# FPGA.net
KiCad netlist of a schematic drawn in Altium Designer
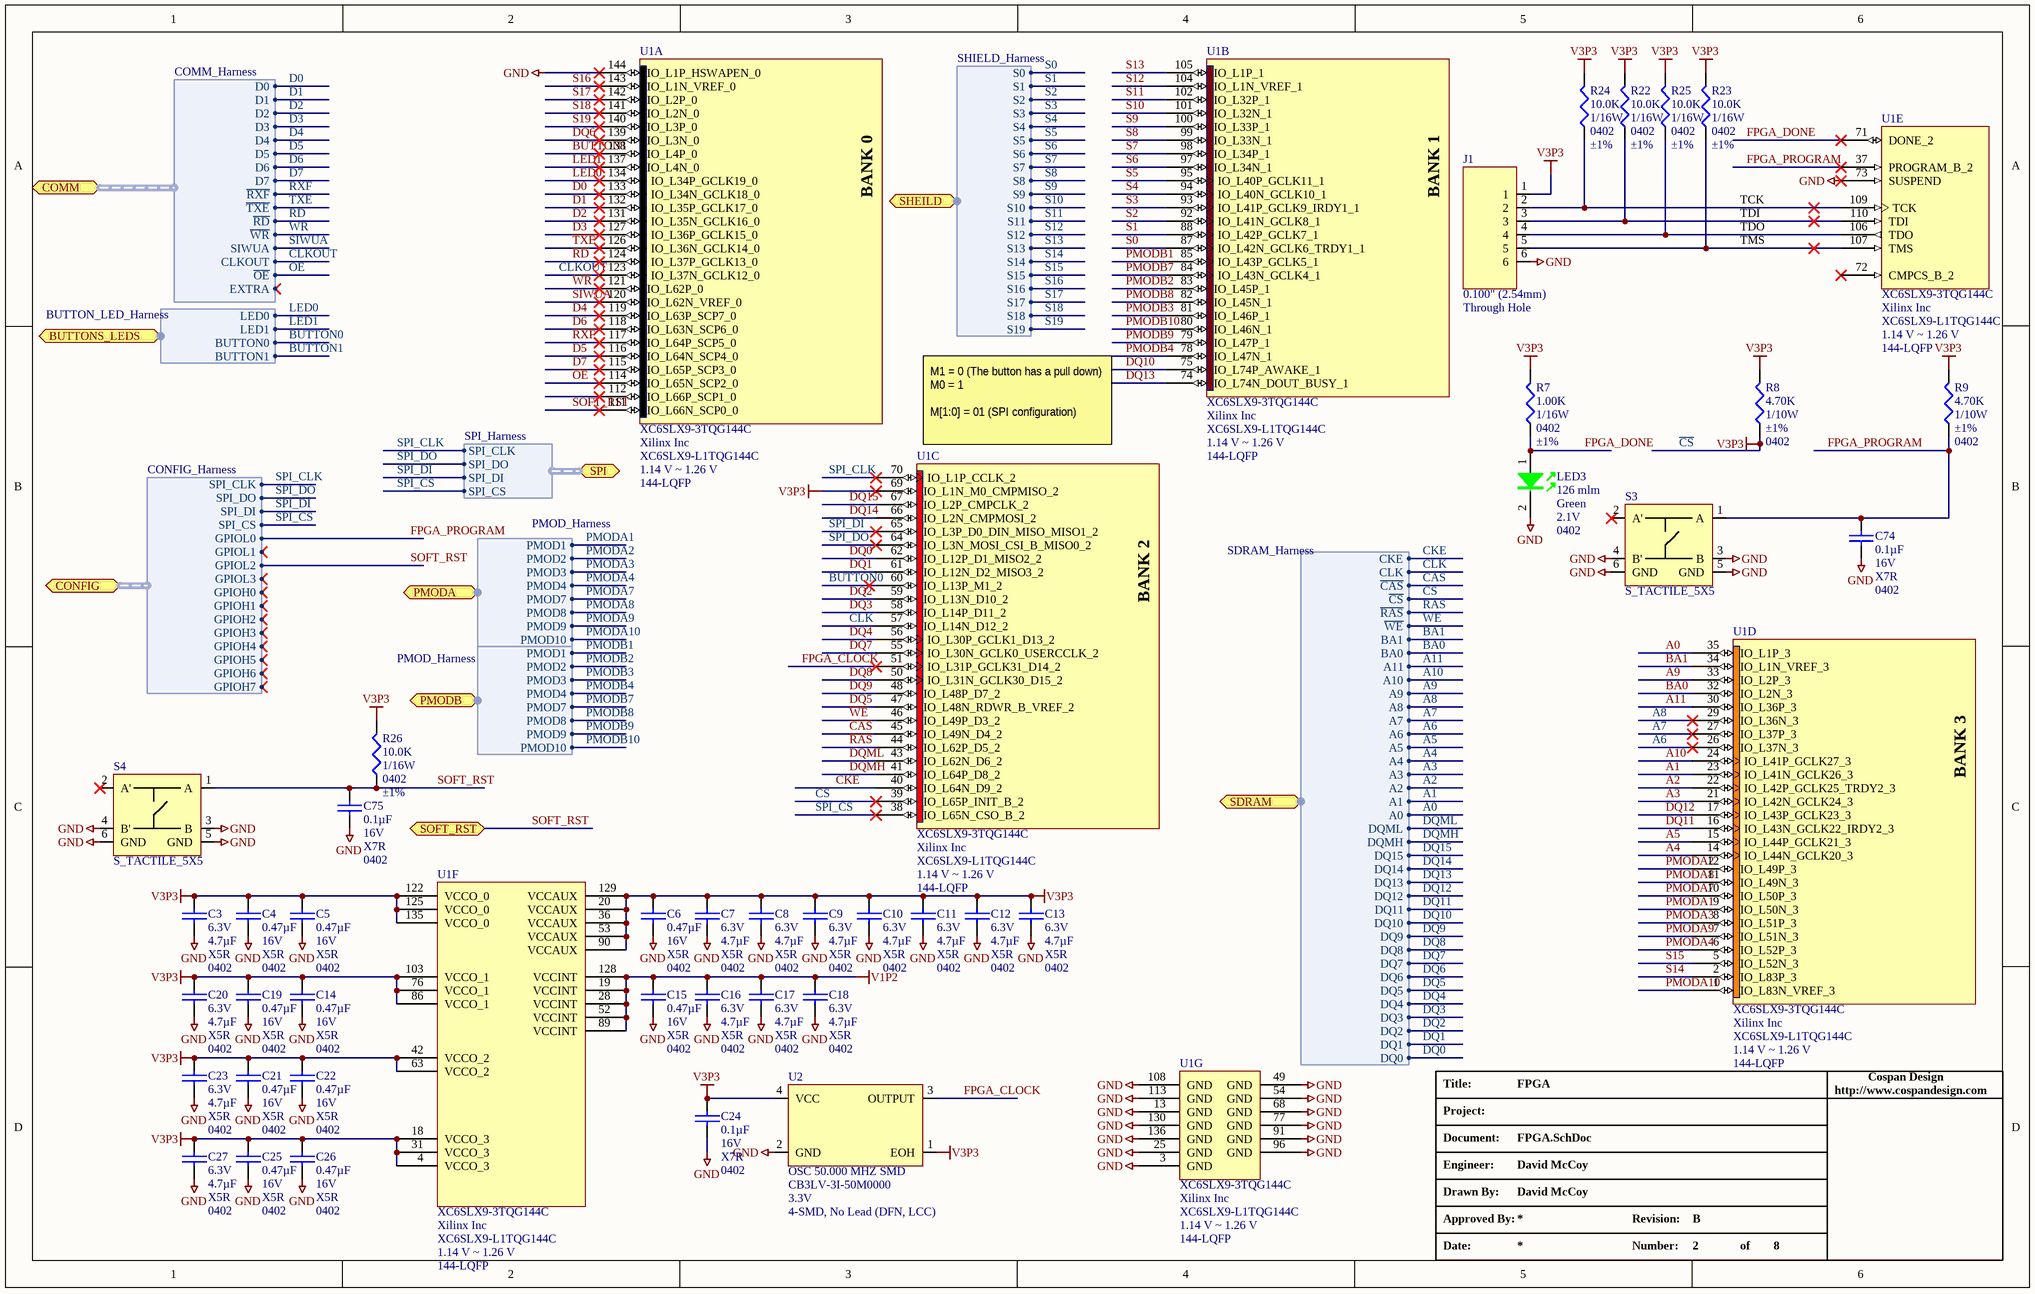
[diagram p0: FPGA.SchDoc]

(export (version "E")
  (design (tool "Eeschema 10.0.6"))
  (components
    (comp (ref "C3")
      (value "4.7uF")
      (footprint "C_ERA-0402")
      (description "CAP CER 4.7UF 6.3V X5R 0402")
      (fields
        (field (name "MANUFACTURER") "Murata Electronics North America")
        (field (name "MANUFACTURER PART NUMBER") "GRM155R60J475ME87D")
        (field (name "VOLTAGE - RATED") "6.3V")
        (field (name "CAPACITANCE") "4.7µF")
        (field (name "TEMPERATURE COEFFICIENT") "X5R")
        (field (name "PACKAGE / CASE") "0402")
      )
      (libsource (lib "Main LibraryX") (part "C_0402_4.7UF"))
    )
    (comp (ref "C4")
      (value "0.47uF")
      (footprint "C_ERA-0402")
      (description "CAP CER .47UF 16V X5R 0402")
      (fields
        (field (name "TOLERANCE") "±10%")
        (field (name "MANUFACTURER") "TDK Corporation")
        (field (name "CAPACITANCE") "0.47µF")
        (field (name "VOLTAGE - RATED") "16V")
        (field (name "TEMPERATURE COEFFICIENT") "X5R")
        (field (name "PACKAGE / CASE") "0402")
      )
      (libsource (lib "Main LibraryX") (part "C_0402_0.47UF"))
    )
    (comp (ref "C5")
      (value "0.47uF")
      (footprint "C_ERA-0402")
      (description "CAP CER .47UF 16V X5R 0402")
      (fields
        (field (name "TOLERANCE") "±10%")
        (field (name "MANUFACTURER") "TDK Corporation")
        (field (name "CAPACITANCE") "0.47µF")
        (field (name "VOLTAGE - RATED") "16V")
        (field (name "TEMPERATURE COEFFICIENT") "X5R")
        (field (name "PACKAGE / CASE") "0402")
      )
      (libsource (lib "Main LibraryX") (part "C_0402_0.47UF"))
    )
    (comp (ref "C6")
      (value "0.47uF")
      (footprint "C_ERA-0402")
      (description "CAP CER .47UF 16V X5R 0402")
      (fields
        (field (name "TOLERANCE") "±10%")
        (field (name "MANUFACTURER") "TDK Corporation")
        (field (name "CAPACITANCE") "0.47µF")
        (field (name "VOLTAGE - RATED") "16V")
        (field (name "TEMPERATURE COEFFICIENT") "X5R")
        (field (name "PACKAGE / CASE") "0402")
      )
      (libsource (lib "Main LibraryX") (part "C_0402_0.47UF"))
    )
    (comp (ref "C7")
      (value "4.7uF")
      (footprint "C_ERA-0402")
      (description "CAP CER 4.7UF 6.3V X5R 0402")
      (fields
        (field (name "MANUFACTURER") "Murata Electronics North America")
        (field (name "MANUFACTURER PART NUMBER") "GRM155R60J475ME87D")
        (field (name "VOLTAGE - RATED") "6.3V")
        (field (name "CAPACITANCE") "4.7µF")
        (field (name "TEMPERATURE COEFFICIENT") "X5R")
        (field (name "PACKAGE / CASE") "0402")
      )
      (libsource (lib "Main LibraryX") (part "C_0402_4.7UF"))
    )
    (comp (ref "C8")
      (value "4.7uF")
      (footprint "C_ERA-0402")
      (description "CAP CER 4.7UF 6.3V X5R 0402")
      (fields
        (field (name "MANUFACTURER") "Murata Electronics North America")
        (field (name "MANUFACTURER PART NUMBER") "GRM155R60J475ME87D")
        (field (name "VOLTAGE - RATED") "6.3V")
        (field (name "CAPACITANCE") "4.7µF")
        (field (name "TEMPERATURE COEFFICIENT") "X5R")
        (field (name "PACKAGE / CASE") "0402")
      )
      (libsource (lib "Main LibraryX") (part "C_0402_4.7UF"))
    )
    (comp (ref "C9")
      (value "4.7uF")
      (footprint "C_ERA-0402")
      (description "CAP CER 4.7UF 6.3V X5R 0402")
      (fields
        (field (name "MANUFACTURER") "Murata Electronics North America")
        (field (name "MANUFACTURER PART NUMBER") "GRM155R60J475ME87D")
        (field (name "VOLTAGE - RATED") "6.3V")
        (field (name "CAPACITANCE") "4.7µF")
        (field (name "TEMPERATURE COEFFICIENT") "X5R")
        (field (name "PACKAGE / CASE") "0402")
      )
      (libsource (lib "Main LibraryX") (part "C_0402_4.7UF"))
    )
    (comp (ref "C10")
      (value "4.7uF")
      (footprint "C_ERA-0402")
      (description "CAP CER 4.7UF 6.3V X5R 0402")
      (fields
        (field (name "MANUFACTURER") "Murata Electronics North America")
        (field (name "MANUFACTURER PART NUMBER") "GRM155R60J475ME87D")
        (field (name "VOLTAGE - RATED") "6.3V")
        (field (name "CAPACITANCE") "4.7µF")
        (field (name "TEMPERATURE COEFFICIENT") "X5R")
        (field (name "PACKAGE / CASE") "0402")
      )
      (libsource (lib "Main LibraryX") (part "C_0402_4.7UF"))
    )
    (comp (ref "C11")
      (value "4.7uF")
      (footprint "C_ERA-0402")
      (description "CAP CER 4.7UF 6.3V X5R 0402")
      (fields
        (field (name "MANUFACTURER") "Murata Electronics North America")
        (field (name "MANUFACTURER PART NUMBER") "GRM155R60J475ME87D")
        (field (name "VOLTAGE - RATED") "6.3V")
        (field (name "CAPACITANCE") "4.7µF")
        (field (name "TEMPERATURE COEFFICIENT") "X5R")
        (field (name "PACKAGE / CASE") "0402")
      )
      (libsource (lib "Main LibraryX") (part "C_0402_4.7UF"))
    )
    (comp (ref "C12")
      (value "4.7uF")
      (footprint "C_ERA-0402")
      (description "CAP CER 4.7UF 6.3V X5R 0402")
      (fields
        (field (name "MANUFACTURER") "Murata Electronics North America")
        (field (name "MANUFACTURER PART NUMBER") "GRM155R60J475ME87D")
        (field (name "VOLTAGE - RATED") "6.3V")
        (field (name "CAPACITANCE") "4.7µF")
        (field (name "TEMPERATURE COEFFICIENT") "X5R")
        (field (name "PACKAGE / CASE") "0402")
      )
      (libsource (lib "Main LibraryX") (part "C_0402_4.7UF"))
    )
    (comp (ref "C13")
      (value "4.7uF")
      (footprint "C_ERA-0402")
      (description "CAP CER 4.7UF 6.3V X5R 0402")
      (fields
        (field (name "MANUFACTURER") "Murata Electronics North America")
        (field (name "MANUFACTURER PART NUMBER") "GRM155R60J475ME87D")
        (field (name "VOLTAGE - RATED") "6.3V")
        (field (name "CAPACITANCE") "4.7µF")
        (field (name "TEMPERATURE COEFFICIENT") "X5R")
        (field (name "PACKAGE / CASE") "0402")
      )
      (libsource (lib "Main LibraryX") (part "C_0402_4.7UF"))
    )
    (comp (ref "C14")
      (value "0.47uF")
      (footprint "C_ERA-0402")
      (description "CAP CER .47UF 16V X5R 0402")
      (fields
        (field (name "TOLERANCE") "±10%")
        (field (name "MANUFACTURER") "TDK Corporation")
        (field (name "CAPACITANCE") "0.47µF")
        (field (name "VOLTAGE - RATED") "16V")
        (field (name "TEMPERATURE COEFFICIENT") "X5R")
        (field (name "PACKAGE / CASE") "0402")
      )
      (libsource (lib "Main LibraryX") (part "C_0402_0.47UF"))
    )
    (comp (ref "C15")
      (value "0.47uF")
      (footprint "C_ERA-0402")
      (description "CAP CER .47UF 16V X5R 0402")
      (fields
        (field (name "TOLERANCE") "±10%")
        (field (name "MANUFACTURER") "TDK Corporation")
        (field (name "CAPACITANCE") "0.47µF")
        (field (name "VOLTAGE - RATED") "16V")
        (field (name "TEMPERATURE COEFFICIENT") "X5R")
        (field (name "PACKAGE / CASE") "0402")
      )
      (libsource (lib "Main LibraryX") (part "C_0402_0.47UF"))
    )
    (comp (ref "C16")
      (value "4.7uF")
      (footprint "C_ERA-0402")
      (description "CAP CER 4.7UF 6.3V X5R 0402")
      (fields
        (field (name "MANUFACTURER") "Murata Electronics North America")
        (field (name "MANUFACTURER PART NUMBER") "GRM155R60J475ME87D")
        (field (name "VOLTAGE - RATED") "6.3V")
        (field (name "CAPACITANCE") "4.7µF")
        (field (name "TEMPERATURE COEFFICIENT") "X5R")
        (field (name "PACKAGE / CASE") "0402")
      )
      (libsource (lib "Main LibraryX") (part "C_0402_4.7UF"))
    )
    (comp (ref "C17")
      (value "4.7uF")
      (footprint "C_ERA-0402")
      (description "CAP CER 4.7UF 6.3V X5R 0402")
      (fields
        (field (name "MANUFACTURER") "Murata Electronics North America")
        (field (name "MANUFACTURER PART NUMBER") "GRM155R60J475ME87D")
        (field (name "VOLTAGE - RATED") "6.3V")
        (field (name "CAPACITANCE") "4.7µF")
        (field (name "TEMPERATURE COEFFICIENT") "X5R")
        (field (name "PACKAGE / CASE") "0402")
      )
      (libsource (lib "Main LibraryX") (part "C_0402_4.7UF"))
    )
    (comp (ref "C18")
      (value "4.7uF")
      (footprint "C_ERA-0402")
      (description "CAP CER 4.7UF 6.3V X5R 0402")
      (fields
        (field (name "MANUFACTURER") "Murata Electronics North America")
        (field (name "MANUFACTURER PART NUMBER") "GRM155R60J475ME87D")
        (field (name "VOLTAGE - RATED") "6.3V")
        (field (name "CAPACITANCE") "4.7µF")
        (field (name "TEMPERATURE COEFFICIENT") "X5R")
        (field (name "PACKAGE / CASE") "0402")
      )
      (libsource (lib "Main LibraryX") (part "C_0402_4.7UF"))
    )
    (comp (ref "C19")
      (value "0.47uF")
      (footprint "C_ERA-0402")
      (description "CAP CER .47UF 16V X5R 0402")
      (fields
        (field (name "TOLERANCE") "±10%")
        (field (name "MANUFACTURER") "TDK Corporation")
        (field (name "CAPACITANCE") "0.47µF")
        (field (name "VOLTAGE - RATED") "16V")
        (field (name "TEMPERATURE COEFFICIENT") "X5R")
        (field (name "PACKAGE / CASE") "0402")
      )
      (libsource (lib "Main LibraryX") (part "C_0402_0.47UF"))
    )
    (comp (ref "C20")
      (value "4.7uF")
      (footprint "C_ERA-0402")
      (description "CAP CER 4.7UF 6.3V X5R 0402")
      (fields
        (field (name "MANUFACTURER") "Murata Electronics North America")
        (field (name "MANUFACTURER PART NUMBER") "GRM155R60J475ME87D")
        (field (name "VOLTAGE - RATED") "6.3V")
        (field (name "CAPACITANCE") "4.7µF")
        (field (name "TEMPERATURE COEFFICIENT") "X5R")
        (field (name "PACKAGE / CASE") "0402")
      )
      (libsource (lib "Main LibraryX") (part "C_0402_4.7UF"))
    )
    (comp (ref "C21")
      (value "0.47uF")
      (footprint "C_ERA-0402")
      (description "CAP CER .47UF 16V X5R 0402")
      (fields
        (field (name "TOLERANCE") "±10%")
        (field (name "MANUFACTURER") "TDK Corporation")
        (field (name "CAPACITANCE") "0.47µF")
        (field (name "VOLTAGE - RATED") "16V")
        (field (name "TEMPERATURE COEFFICIENT") "X5R")
        (field (name "PACKAGE / CASE") "0402")
      )
      (libsource (lib "Main LibraryX") (part "C_0402_0.47UF"))
    )
    (comp (ref "C22")
      (value "0.47uF")
      (footprint "C_ERA-0402")
      (description "CAP CER .47UF 16V X5R 0402")
      (fields
        (field (name "TOLERANCE") "±10%")
        (field (name "MANUFACTURER") "TDK Corporation")
        (field (name "CAPACITANCE") "0.47µF")
        (field (name "VOLTAGE - RATED") "16V")
        (field (name "TEMPERATURE COEFFICIENT") "X5R")
        (field (name "PACKAGE / CASE") "0402")
      )
      (libsource (lib "Main LibraryX") (part "C_0402_0.47UF"))
    )
    (comp (ref "C23")
      (value "4.7uF")
      (footprint "C_ERA-0402")
      (description "CAP CER 4.7UF 6.3V X5R 0402")
      (fields
        (field (name "MANUFACTURER") "Murata Electronics North America")
        (field (name "MANUFACTURER PART NUMBER") "GRM155R60J475ME87D")
        (field (name "VOLTAGE - RATED") "6.3V")
        (field (name "CAPACITANCE") "4.7µF")
        (field (name "TEMPERATURE COEFFICIENT") "X5R")
        (field (name "PACKAGE / CASE") "0402")
      )
      (libsource (lib "Main LibraryX") (part "C_0402_4.7UF"))
    )
    (comp (ref "C24")
      (value "0.1uF")
      (footprint "C_ERA-0402")
      (description "CAP CER .10UF 16V X7R 0402")
      (fields
        (field (name "MANUFACTURER") "TDK Corporation")
        (field (name "MANUFACTURER PART NUMBER") "C1005X7R1C104K")
        (field (name "CAPACITANCE") "0.1µF")
        (field (name "VOLTAGE - RATED") "16V")
        (field (name "TEMPERATURE COEFFICIENT") "X7R")
        (field (name "PACKAGE / CASE") "0402")
      )
      (libsource (lib "Main LibraryX") (part "C_0402_0.1UF_16V"))
    )
    (comp (ref "C25")
      (value "0.47uF")
      (footprint "C_ERA-0402")
      (description "CAP CER .47UF 16V X5R 0402")
      (fields
        (field (name "TOLERANCE") "±10%")
        (field (name "MANUFACTURER") "TDK Corporation")
        (field (name "CAPACITANCE") "0.47µF")
        (field (name "VOLTAGE - RATED") "16V")
        (field (name "TEMPERATURE COEFFICIENT") "X5R")
        (field (name "PACKAGE / CASE") "0402")
      )
      (libsource (lib "Main LibraryX") (part "C_0402_0.47UF"))
    )
    (comp (ref "C26")
      (value "0.47uF")
      (footprint "C_ERA-0402")
      (description "CAP CER .47UF 16V X5R 0402")
      (fields
        (field (name "TOLERANCE") "±10%")
        (field (name "MANUFACTURER") "TDK Corporation")
        (field (name "CAPACITANCE") "0.47µF")
        (field (name "VOLTAGE - RATED") "16V")
        (field (name "TEMPERATURE COEFFICIENT") "X5R")
        (field (name "PACKAGE / CASE") "0402")
      )
      (libsource (lib "Main LibraryX") (part "C_0402_0.47UF"))
    )
    (comp (ref "C27")
      (value "4.7uF")
      (footprint "C_ERA-0402")
      (description "CAP CER 4.7UF 6.3V X5R 0402")
      (fields
        (field (name "MANUFACTURER") "Murata Electronics North America")
        (field (name "MANUFACTURER PART NUMBER") "GRM155R60J475ME87D")
        (field (name "VOLTAGE - RATED") "6.3V")
        (field (name "CAPACITANCE") "4.7µF")
        (field (name "TEMPERATURE COEFFICIENT") "X5R")
        (field (name "PACKAGE / CASE") "0402")
      )
      (libsource (lib "Main LibraryX") (part "C_0402_4.7UF"))
    )
    (comp (ref "C74")
      (value "0.1uF")
      (footprint "C_ERA-0402")
      (description "CAP CER .10UF 16V X7R 0402")
      (fields
        (field (name "MANUFACTURER") "TDK Corporation")
        (field (name "MANUFACTURER PART NUMBER") "C1005X7R1C104K")
        (field (name "CAPACITANCE") "0.1µF")
        (field (name "VOLTAGE - RATED") "16V")
        (field (name "TEMPERATURE COEFFICIENT") "X7R")
        (field (name "PACKAGE / CASE") "0402")
      )
      (libsource (lib "Main LibraryX") (part "C_0402_0.1UF_16V"))
    )
    (comp (ref "C75")
      (value "0.1uF")
      (footprint "C_ERA-0402")
      (description "CAP CER .10UF 16V X7R 0402")
      (fields
        (field (name "MANUFACTURER") "TDK Corporation")
        (field (name "MANUFACTURER PART NUMBER") "C1005X7R1C104K")
        (field (name "CAPACITANCE") "0.1µF")
        (field (name "VOLTAGE - RATED") "16V")
        (field (name "TEMPERATURE COEFFICIENT") "X7R")
        (field (name "PACKAGE / CASE") "0402")
      )
      (libsource (lib "Main LibraryX") (part "C_0402_0.1UF_16V"))
    )
    (comp (ref "J1")
      (value "J_HDR1X6_THRHOLE_VERT")
      (footprint "HDR_1X6")
      (description "CONN HEADER .100\" 12POS TIN PCB")
      (fields
        (field (name "MANUFACTURER") "Samtec")
        (field (name "MANUFACTURER PART NUMBER") "TSW-106-07-T-S")
        (field (name "PITCH") "0.100\" (2.54mm)")
        (field (name "MOUNTING TYPE") "Through Hole")
      )
      (libsource (lib "Main LibraryX") (part "J_HDR1X6_THRHOLE_VERT"))
    )
    (comp (ref "LED3")
      (value "LED_GRN_0402")
      (footprint "DIOM1005X07L_GREEN")
      (description "LED 1X0.5MM 570NM GN WTR CLR SMD")
      (fields
        (field (name "MANUFACTURER") "Kingbright Corp")
        (field (name "MANUFACTURER PART NUMBER") "APHHS1005CGCK")
        (field (name "LUMINOUS FLUX @ CURRENT - TEST") "126 mlm")
        (field (name "COLOR") "Green")
        (field (name "VOLTAGE - FORWARD (VF) TYP") "2.1V")
        (field (name "PACKAGE / CASE") "0402")
      )
      (libsource (lib "Main Library") (part "LED_GRN_0402"))
    )
    (comp (ref "R7")
      (value "1.0k Ohms")
      (footprint "ERA-0402")
      (description "RES 1.00K OHM 1/16W 1% 0402 SMD")
      (fields
        (field (name "MANUFACTURER") "Yageo")
        (field (name "MANUFACTURER PART NUMBER") "RC0402FR-071KL")
        (field (name "RESISTANCE IN OHMS") "1.00K")
        (field (name "POWER (WATTS)") "1/16W")
        (field (name "CASE") "0402")
        (field (name "TOLERANCE") "±1%")
      )
      (libsource (lib "Main Library") (part "R_0402_1.0K"))
    )
    (comp (ref "R8")
      (value "4.7k Ohms")
      (footprint "ERA-0402")
      (description "RES 4.70K OHM 1/10W 1% 0402 SMD")
      (fields
        (field (name "MANUFACTURER") "Yageo")
        (field (name "MANUFACTURER PART NUMBER") "RC0402FR-074K7L")
        (field (name "RESISTANCE IN OHMS") "4.70K")
        (field (name "POWER (WATTS)") "1/10W")
        (field (name "TOLERANCE") "±1%")
        (field (name "CASE") "0402")
      )
      (libsource (lib "Main LibraryX") (part "R_0402_4.70K"))
    )
    (comp (ref "R9")
      (value "4.7k Ohms")
      (footprint "ERA-0402")
      (description "RES 4.70K OHM 1/10W 1% 0402 SMD")
      (fields
        (field (name "MANUFACTURER") "Yageo")
        (field (name "MANUFACTURER PART NUMBER") "RC0402FR-074K7L")
        (field (name "RESISTANCE IN OHMS") "4.70K")
        (field (name "POWER (WATTS)") "1/10W")
        (field (name "TOLERANCE") "±1%")
        (field (name "CASE") "0402")
      )
      (libsource (lib "Main LibraryX") (part "R_0402_4.70K"))
    )
    (comp (ref "R22")
      (value "R_0402_10.0K")
      (footprint "ERA-0402")
      (description "RES 10.0K OHM 1/16W 1% 0402 SMD")
      (fields
        (field (name "MANUFACTURER") "Stackpole Electronics Inc")
        (field (name "MANUFACTURER PART NUMBER") "RMCF0402FT10K0")
        (field (name "RESISTANCE IN OHMS") "10.0K")
        (field (name "POWER (WATTS)") "1/16W")
        (field (name "CASE") "0402")
        (field (name "TOLERANCE") "±1%")
      )
      (libsource (lib "Main LibraryX") (part "R_0402_10.0K"))
    )
    (comp (ref "R23")
      (value "R_0402_10.0K")
      (footprint "ERA-0402")
      (description "RES 10.0K OHM 1/16W 1% 0402 SMD")
      (fields
        (field (name "MANUFACTURER") "Stackpole Electronics Inc")
        (field (name "MANUFACTURER PART NUMBER") "RMCF0402FT10K0")
        (field (name "RESISTANCE IN OHMS") "10.0K")
        (field (name "POWER (WATTS)") "1/16W")
        (field (name "CASE") "0402")
        (field (name "TOLERANCE") "±1%")
      )
      (libsource (lib "Main LibraryX") (part "R_0402_10.0K"))
    )
    (comp (ref "R24")
      (value "R_0402_10.0K")
      (footprint "ERA-0402")
      (description "RES 10.0K OHM 1/16W 1% 0402 SMD")
      (fields
        (field (name "MANUFACTURER") "Stackpole Electronics Inc")
        (field (name "MANUFACTURER PART NUMBER") "RMCF0402FT10K0")
        (field (name "RESISTANCE IN OHMS") "10.0K")
        (field (name "POWER (WATTS)") "1/16W")
        (field (name "CASE") "0402")
        (field (name "TOLERANCE") "±1%")
      )
      (libsource (lib "Main LibraryX") (part "R_0402_10.0K"))
    )
    (comp (ref "R25")
      (value "R_0402_10.0K")
      (footprint "ERA-0402")
      (description "RES 10.0K OHM 1/16W 1% 0402 SMD")
      (fields
        (field (name "MANUFACTURER") "Stackpole Electronics Inc")
        (field (name "MANUFACTURER PART NUMBER") "RMCF0402FT10K0")
        (field (name "RESISTANCE IN OHMS") "10.0K")
        (field (name "POWER (WATTS)") "1/16W")
        (field (name "CASE") "0402")
        (field (name "TOLERANCE") "±1%")
      )
      (libsource (lib "Main LibraryX") (part "R_0402_10.0K"))
    )
    (comp (ref "R26")
      (value "R_0402_10.0K")
      (footprint "ERA-0402")
      (description "RES 10.0K OHM 1/16W 1% 0402 SMD")
      (fields
        (field (name "MANUFACTURER") "Stackpole Electronics Inc")
        (field (name "MANUFACTURER PART NUMBER") "RMCF0402FT10K0")
        (field (name "RESISTANCE IN OHMS") "10.0K")
        (field (name "POWER (WATTS)") "1/16W")
        (field (name "CASE") "0402")
        (field (name "TOLERANCE") "±1%")
      )
      (libsource (lib "Main LibraryX") (part "R_0402_10.0K"))
    )
    (comp (ref "S3")
      (value "S_TACTILE_5X5")
      (footprint "TACTILE_BUTTON_5X5")
      (description "SWITCH LT 1.5MM HT 160GF SMD")
      (fields
        (field (name "MANUFACTURER") "Panasonic - ECG")
        (field (name "MANUFACTURER PART NUMBER") "EVQ-PLHA15")
      )
      (libsource (lib "Main Library") (part "S_TACTILE_5X5"))
    )
    (comp (ref "S4")
      (value "S_TACTILE_5X5")
      (footprint "TACTILE_BUTTON_5X5")
      (description "SWITCH LT 1.5MM HT 160GF SMD")
      (fields
        (field (name "MANUFACTURER") "Panasonic - ECG")
        (field (name "MANUFACTURER PART NUMBER") "EVQ-PLHA15")
      )
      (libsource (lib "Main Library") (part "S_TACTILE_5X5"))
    )
    (comp (ref "U1")
      (value "XC6SLX9-3TQG144C")
      (footprint "TQG144_N")
      (description "IC FPAG SPARTAN 6 9K 144TQFP")
      (fields
        (field (name "MANUFACTURER") "Xilinx Inc")
        (field (name "MANUFACTURER PART NUMBER") "XC6SLX9-L1TQG144C")
        (field (name "VOLTAGE - SUPPLY") "1.14 V ~ 1.26 V")
        (field (name "PACKAGE / CASE") "144-LQFP")
      )
      (libsource (lib "") (part "U_XC6SLX9-3TQG144C_1"))
    )
    (comp (ref "U2")
      (value "OSC 50.000 MHZ SMD")
      (footprint "SMD_OSC_12MHZ")
      (description "OSC 50.0000 MHZ 3.3V SMD")
      (fields
        (field (name "MANUFACTURER") "CTS-Frequency Controls")
        (field (name "MANUFACTURER PART NUMBER") "CB3LV-3I-50M0000")
        (field (name "SUPPLY VOLTAGE") "3.3V")
        (field (name "PACKAGE / CASE") "4-SMD, No Lead (DFN, LCC)")
      )
      (libsource (lib "Main Library") (part "U_OSC_50MHZ_SMD"))
    )
  )
  (nets
    (net (code "8") (name "/A0") (class "Default")
      (node (ref "U1") (pin "35") (pinfunction "IO_L1P_3_35") (pintype "bidirectional"))
    )
    (net (code "9") (name "/A1") (class "Default")
      (node (ref "U1") (pin "23") (pinfunction "IO_L41N_GCLK26_3_23") (pintype "bidirectional"))
    )
    (net (code "10") (name "/A2") (class "Default")
      (node (ref "U1") (pin "22") (pinfunction "IO_L42P_GCLK25_TRDY2_3_22") (pintype "bidirectional"))
    )
    (net (code "11") (name "/A3") (class "Default")
      (node (ref "U1") (pin "21") (pinfunction "IO_L42N_GCLK24_3_21") (pintype "bidirectional"))
    )
    (net (code "12") (name "/A4") (class "Default")
      (node (ref "U1") (pin "14") (pinfunction "IO_L44N_GCLK20_3_14") (pintype "bidirectional"))
    )
    (net (code "13") (name "/A5") (class "Default")
      (node (ref "U1") (pin "15") (pinfunction "IO_L44P_GCLK21_3_15") (pintype "bidirectional"))
    )
    (net (code "14") (name "/A6") (class "Default")
      (node (ref "U1") (pin "26") (pinfunction "IO_L37N_3_26") (pintype "bidirectional"))
    )
    (net (code "15") (name "/A7") (class "Default")
      (node (ref "U1") (pin "27") (pinfunction "IO_L37P_3_27") (pintype "bidirectional"))
    )
    (net (code "16") (name "/A8") (class "Default")
      (node (ref "U1") (pin "29") (pinfunction "IO_L36N_3_29") (pintype "bidirectional"))
    )
    (net (code "17") (name "/A9") (class "Default")
      (node (ref "U1") (pin "33") (pinfunction "IO_L2P_3_33") (pintype "bidirectional"))
    )
    (net (code "18") (name "/A10") (class "Default")
      (node (ref "U1") (pin "24") (pinfunction "IO_L41P_GCLK27_3_24") (pintype "bidirectional"))
    )
    (net (code "19") (name "/A11") (class "Default")
      (node (ref "U1") (pin "30") (pinfunction "IO_L36P_3_30") (pintype "bidirectional"))
    )
    (net (code "20") (name "/BA0") (class "Default")
      (node (ref "U1") (pin "32") (pinfunction "IO_L2N_3_32") (pintype "bidirectional"))
    )
    (net (code "21") (name "/BA1") (class "Default")
      (node (ref "U1") (pin "34") (pinfunction "IO_L1N_VREF_3_34") (pintype "bidirectional"))
    )
    (net (code "22") (name "/BUTTON0") (class "Default")
      (node (ref "U1") (pin "60") (pinfunction "IO_L13P_M1_2_60") (pintype "bidirectional"))
    )
    (net (code "23") (name "/BUTTON1") (class "Default")
      (node (ref "U1") (pin "138") (pinfunction "IO_L4P_0_138") (pintype "bidirectional"))
    )
    (net (code "24") (name "/CKE") (class "Default")
      (node (ref "U1") (pin "40") (pinfunction "IO_L64N_D9_2_40") (pintype "bidirectional"))
    )
    (net (code "25") (name "/CLK") (class "Default")
      (node (ref "U1") (pin "57") (pinfunction "IO_L14N_D12_2_57") (pintype "bidirectional"))
    )
    (net (code "26") (name "/CLKOUT") (class "Default")
      (node (ref "U1") (pin "123") (pinfunction "IO_L37N_GCLK12_0_123") (pintype "bidirectional+no_connect"))
    )
    (net (code "27") (name "/D0") (class "Default")
      (node (ref "U1") (pin "133") (pinfunction "IO_L34N_GCLK18_0_133") (pintype "bidirectional"))
    )
    (net (code "28") (name "/D1") (class "Default")
      (node (ref "U1") (pin "132") (pinfunction "IO_L35P_GCLK17_0_132") (pintype "bidirectional"))
    )
    (net (code "29") (name "/D2") (class "Default")
      (node (ref "U1") (pin "131") (pinfunction "IO_L35N_GCLK16_0_131") (pintype "bidirectional"))
    )
    (net (code "30") (name "/D3") (class "Default")
      (node (ref "U1") (pin "127") (pinfunction "IO_L36P_GCLK15_0_127") (pintype "bidirectional+no_connect"))
    )
    (net (code "31") (name "/D4") (class "Default")
      (node (ref "U1") (pin "119") (pinfunction "IO_L63P_SCP7_0_119") (pintype "bidirectional+no_connect"))
    )
    (net (code "32") (name "/D5") (class "Default")
      (node (ref "U1") (pin "116") (pinfunction "IO_L64N_SCP4_0_116") (pintype "bidirectional"))
    )
    (net (code "33") (name "/D6") (class "Default")
      (node (ref "U1") (pin "118") (pinfunction "IO_L63N_SCP6_0_118") (pintype "bidirectional+no_connect"))
    )
    (net (code "34") (name "/D7") (class "Default")
      (node (ref "U1") (pin "115") (pinfunction "IO_L65P_SCP3_0_115") (pintype "bidirectional"))
    )
    (net (code "35") (name "/DQ0") (class "Default")
      (node (ref "U1") (pin "62") (pinfunction "IO_L12P_D1_MISO2_2_62") (pintype "bidirectional"))
    )
    (net (code "36") (name "/DQ1") (class "Default")
      (node (ref "U1") (pin "61") (pinfunction "IO_L12N_D2_MISO3_2_61") (pintype "bidirectional"))
    )
    (net (code "37") (name "/DQ2") (class "Default")
      (node (ref "U1") (pin "59") (pinfunction "IO_L13N_D10_2_59") (pintype "bidirectional"))
    )
    (net (code "38") (name "/DQ3") (class "Default")
      (node (ref "U1") (pin "58") (pinfunction "IO_L14P_D11_2_58") (pintype "bidirectional"))
    )
    (net (code "39") (name "/DQ4") (class "Default")
      (node (ref "U1") (pin "56") (pinfunction "IO_L30P_GCLK1_D13_2_56") (pintype "bidirectional"))
    )
    (net (code "40") (name "/DQ5") (class "Default")
      (node (ref "U1") (pin "47") (pinfunction "IO_L48N_RDWR_B_VREF_2_47") (pintype "bidirectional"))
    )
    (net (code "41") (name "/DQ6") (class "Default")
      (node (ref "U1") (pin "139") (pinfunction "IO_L3N_0_139") (pintype "bidirectional+no_connect"))
    )
    (net (code "42") (name "/DQ7") (class "Default")
      (node (ref "U1") (pin "55") (pinfunction "IO_L30N_GCLK0_USERCCLK_2_55") (pintype "bidirectional"))
    )
    (net (code "43") (name "/DQ8") (class "Default")
      (node (ref "U1") (pin "50") (pinfunction "IO_L31N_GCLK30_D15_2_50") (pintype "bidirectional"))
    )
    (net (code "44") (name "/DQ9") (class "Default")
      (node (ref "U1") (pin "48") (pinfunction "IO_L48P_D7_2_48") (pintype "bidirectional"))
    )
    (net (code "45") (name "/DQ10") (class "Default")
      (node (ref "U1") (pin "75") (pinfunction "IO_L74P_AWAKE_1_75") (pintype "bidirectional"))
    )
    (net (code "46") (name "/DQ11") (class "Default")
      (node (ref "U1") (pin "16") (pinfunction "IO_L43N_GCLK22_IRDY2_3_16") (pintype "bidirectional"))
    )
    (net (code "47") (name "/DQ12") (class "Default")
      (node (ref "U1") (pin "17") (pinfunction "IO_L43P_GCLK23_3_17") (pintype "bidirectional"))
    )
    (net (code "48") (name "/DQ13") (class "Default")
      (node (ref "U1") (pin "74") (pinfunction "IO_L74N_DOUT_BUSY_1_74") (pintype "bidirectional"))
    )
    (net (code "49") (name "/DQ14") (class "Default")
      (node (ref "U1") (pin "66") (pinfunction "IO_L2N_CMPMOSI_2_66") (pintype "bidirectional"))
    )
    (net (code "50") (name "/DQ15") (class "Default")
      (node (ref "U1") (pin "67") (pinfunction "IO_L2P_CMPCLK_2_67") (pintype "bidirectional"))
    )
    (net (code "51") (name "/DQMH") (class "Default")
      (node (ref "U1") (pin "41") (pinfunction "IO_L64P_D8_2_41") (pintype "bidirectional"))
    )
    (net (code "52") (name "/DQML") (class "Default")
      (node (ref "U1") (pin "43") (pinfunction "IO_L62N_D6_2_43") (pintype "bidirectional"))
    )
    (net (code "53") (name "/FPGA_CLOCK") (class "Default")
      (node (ref "U1") (pin "51") (pinfunction "IO_L31P_GCLK31_D14_2_51") (pintype "bidirectional"))
      (node (ref "U2") (pin "3") (pinfunction "OUTPUT_3") (pintype "passive"))
    )
    (net (code "54") (name "/FPGA_DONE") (class "Default")
      (node (ref "LED3") (pin "1") (pinfunction "1_1") (pintype "passive"))
      (node (ref "R7") (pin "2") (pinfunction "2_2") (pintype "passive"))
      (node (ref "U1") (pin "71") (pinfunction "DONE_2_71") (pintype "bidirectional"))
    )
    (net (code "55") (name "/FPGA_PROGRAM") (class "Default")
      (node (ref "C74") (pin "2") (pinfunction "2_2") (pintype "passive"))
      (node (ref "R9") (pin "2") (pinfunction "2_2") (pintype "passive"))
      (node (ref "S3") (pin "1") (pinfunction "A_1") (pintype "passive"))
      (node (ref "U1") (pin "37") (pinfunction "PROGRAM_B_2_37") (pintype "input"))
    )
    (net (code "56") (name "/LED0") (class "Default")
      (node (ref "U1") (pin "134") (pinfunction "IO_L34P_GCLK19_0_134") (pintype "bidirectional"))
    )
    (net (code "57") (name "/LED1") (class "Default")
      (node (ref "U1") (pin "137") (pinfunction "IO_L4N_0_137") (pintype "bidirectional"))
    )
    (net (code "58") (name "/PMODA1") (class "Default")
      (node (ref "U1") (pin "9") (pinfunction "IO_L50N_3_9") (pintype "bidirectional"))
    )
    (net (code "59") (name "/PMODA2") (class "Default")
      (node (ref "U1") (pin "12") (pinfunction "IO_L49P_3_12") (pintype "bidirectional"))
    )
    (net (code "60") (name "/PMODA3") (class "Default")
      (node (ref "U1") (pin "8") (pinfunction "IO_L51P_3_8") (pintype "bidirectional"))
    )
    (net (code "61") (name "/PMODA4") (class "Default")
      (node (ref "U1") (pin "6") (pinfunction "IO_L52P_3_6") (pintype "bidirectional"))
    )
    (net (code "62") (name "/PMODA7") (class "Default")
      (node (ref "U1") (pin "10") (pinfunction "IO_L50P_3_10") (pintype "bidirectional"))
    )
    (net (code "63") (name "/PMODA8") (class "Default")
      (node (ref "U1") (pin "11") (pinfunction "IO_L49N_3_11") (pintype "bidirectional"))
    )
    (net (code "64") (name "/PMODA9") (class "Default")
      (node (ref "U1") (pin "7") (pinfunction "IO_L51N_3_7") (pintype "bidirectional"))
    )
    (net (code "65") (name "/PMODA10") (class "Default")
      (node (ref "U1") (pin "1") (pinfunction "IO_L83N_VREF_3_1") (pintype "bidirectional"))
    )
    (net (code "66") (name "/PMODB1") (class "Default")
      (node (ref "U1") (pin "85") (pinfunction "IO_L43P_GCLK5_1_85") (pintype "bidirectional"))
    )
    (net (code "67") (name "/PMODB2") (class "Default")
      (node (ref "U1") (pin "83") (pinfunction "IO_L45P_1_83") (pintype "bidirectional"))
    )
    (net (code "68") (name "/PMODB3") (class "Default")
      (node (ref "U1") (pin "81") (pinfunction "IO_L46P_1_81") (pintype "bidirectional"))
    )
    (net (code "69") (name "/PMODB4") (class "Default")
      (node (ref "U1") (pin "78") (pinfunction "IO_L47N_1_78") (pintype "bidirectional"))
    )
    (net (code "70") (name "/PMODB7") (class "Default")
      (node (ref "U1") (pin "84") (pinfunction "IO_L43N_GCLK4_1_84") (pintype "bidirectional"))
    )
    (net (code "71") (name "/PMODB8") (class "Default")
      (node (ref "U1") (pin "82") (pinfunction "IO_L45N_1_82") (pintype "bidirectional"))
    )
    (net (code "72") (name "/PMODB9") (class "Default")
      (node (ref "U1") (pin "79") (pinfunction "IO_L47P_1_79") (pintype "bidirectional"))
    )
    (net (code "73") (name "/PMODB10") (class "Default")
      (node (ref "U1") (pin "80") (pinfunction "IO_L46N_1_80") (pintype "bidirectional"))
    )
    (net (code "74") (name "/S0") (class "Default")
      (node (ref "U1") (pin "87") (pinfunction "IO_L42N_GCLK6_TRDY1_1_87") (pintype "bidirectional"))
    )
    (net (code "75") (name "/S1") (class "Default")
      (node (ref "U1") (pin "88") (pinfunction "IO_L42P_GCLK7_1_88") (pintype "bidirectional"))
    )
    (net (code "76") (name "/S2") (class "Default")
      (node (ref "U1") (pin "92") (pinfunction "IO_L41N_GCLK8_1_92") (pintype "bidirectional"))
    )
    (net (code "77") (name "/S3") (class "Default")
      (node (ref "U1") (pin "93") (pinfunction "IO_L41P_GCLK9_IRDY1_1_93") (pintype "bidirectional"))
    )
    (net (code "78") (name "/S4") (class "Default")
      (node (ref "U1") (pin "94") (pinfunction "IO_L40N_GCLK10_1_94") (pintype "bidirectional"))
    )
    (net (code "79") (name "/S5") (class "Default")
      (node (ref "U1") (pin "95") (pinfunction "IO_L40P_GCLK11_1_95") (pintype "bidirectional"))
    )
    (net (code "80") (name "/S6") (class "Default")
      (node (ref "U1") (pin "97") (pinfunction "IO_L34N_1_97") (pintype "bidirectional"))
    )
    (net (code "81") (name "/S7") (class "Default")
      (node (ref "U1") (pin "98") (pinfunction "IO_L34P_1_98") (pintype "bidirectional"))
    )
    (net (code "82") (name "/S8") (class "Default")
      (node (ref "U1") (pin "99") (pinfunction "IO_L33N_1_99") (pintype "bidirectional"))
    )
    (net (code "83") (name "/S9") (class "Default")
      (node (ref "U1") (pin "100") (pinfunction "IO_L33P_1_100") (pintype "bidirectional"))
    )
    (net (code "84") (name "/S10") (class "Default")
      (node (ref "U1") (pin "101") (pinfunction "IO_L32N_1_101") (pintype "bidirectional"))
    )
    (net (code "85") (name "/S11") (class "Default")
      (node (ref "U1") (pin "102") (pinfunction "IO_L32P_1_102") (pintype "bidirectional"))
    )
    (net (code "86") (name "/S12") (class "Default")
      (node (ref "U1") (pin "104") (pinfunction "IO_L1N_VREF_1_104") (pintype "bidirectional"))
    )
    (net (code "87") (name "/S13") (class "Default")
      (node (ref "U1") (pin "105") (pinfunction "IO_L1P_1_105") (pintype "bidirectional"))
    )
    (net (code "88") (name "/S14") (class "Default")
      (node (ref "U1") (pin "2") (pinfunction "IO_L83P_3_2") (pintype "bidirectional"))
    )
    (net (code "89") (name "/S15") (class "Default")
      (node (ref "U1") (pin "5") (pinfunction "IO_L52N_3_5") (pintype "bidirectional"))
    )
    (net (code "90") (name "/S16") (class "Default")
      (node (ref "U1") (pin "143") (pinfunction "IO_L1N_VREF_0_143") (pintype "bidirectional+no_connect"))
    )
    (net (code "91") (name "/S17") (class "Default")
      (node (ref "U1") (pin "142") (pinfunction "IO_L2P_0_142") (pintype "bidirectional+no_connect"))
    )
    (net (code "92") (name "/S18") (class "Default")
      (node (ref "U1") (pin "141") (pinfunction "IO_L2N_0_141") (pintype "bidirectional+no_connect"))
    )
    (net (code "93") (name "/S19") (class "Default")
      (node (ref "U1") (pin "140") (pinfunction "IO_L3P_0_140") (pintype "bidirectional+no_connect"))
    )
    (net (code "94") (name "/SIWUA") (class "Default")
      (node (ref "U1") (pin "120") (pinfunction "IO_L62N_VREF_0_120") (pintype "bidirectional+no_connect"))
    )
    (net (code "95") (name "/SOFT_RST") (class "Default")
      (node (ref "C75") (pin "2") (pinfunction "2_2") (pintype "passive"))
      (node (ref "R26") (pin "2") (pinfunction "2_2") (pintype "passive"))
      (node (ref "S4") (pin "1") (pinfunction "A_1") (pintype "passive"))
      (node (ref "U1") (pin "111") (pinfunction "IO_L66N_SCP0_0_111") (pintype "bidirectional"))
    )
    (net (code "96") (name "/SPI_CLK") (class "Default")
      (node (ref "U1") (pin "70") (pinfunction "IO_L1P_CCLK_2_70") (pintype "bidirectional"))
    )
    (net (code "97") (name "/SPI_CS") (class "Default")
      (node (ref "U1") (pin "38") (pinfunction "IO_L65N_CSO_B_2_38") (pintype "bidirectional"))
    )
    (net (code "98") (name "/SPI_DI") (class "Default")
      (node (ref "U1") (pin "65") (pinfunction "IO_L3P_D0_DIN_MISO_MISO1_2_65") (pintype "bidirectional"))
    )
    (net (code "99") (name "/SPI_DO") (class "Default")
      (node (ref "U1") (pin "64") (pinfunction "IO_L3N_MOSI_CSI_B_MISO0_2_64") (pintype "bidirectional"))
    )
    (net (code "100") (name "/TCK") (class "Default")
      (node (ref "J1") (pin "2") (pinfunction "2_2") (pintype "passive"))
      (node (ref "R24") (pin "2") (pinfunction "2_2") (pintype "passive"))
      (node (ref "U1") (pin "109") (pinfunction "TCK_109") (pintype "input"))
    )
    (net (code "101") (name "/TDI") (class "Default")
      (node (ref "J1") (pin "3") (pinfunction "3_3") (pintype "passive"))
      (node (ref "R22") (pin "2") (pinfunction "2_2") (pintype "passive"))
      (node (ref "U1") (pin "110") (pinfunction "TDI_110") (pintype "input"))
    )
    (net (code "102") (name "/TDO") (class "Default")
      (node (ref "J1") (pin "4") (pinfunction "4_4") (pintype "passive"))
      (node (ref "R25") (pin "2") (pinfunction "2_2") (pintype "passive"))
      (node (ref "U1") (pin "106") (pinfunction "TDO_106") (pintype "output"))
    )
    (net (code "103") (name "/TMS") (class "Default")
      (node (ref "J1") (pin "5") (pinfunction "5_5") (pintype "passive"))
      (node (ref "R23") (pin "2") (pinfunction "2_2") (pintype "passive"))
      (node (ref "U1") (pin "107") (pinfunction "TMS_107") (pintype "input"))
    )
    (net (code "111") (name "/~{CAS}") (class "Default")
      (node (ref "U1") (pin "45") (pinfunction "IO_L49N_D4_2_45") (pintype "bidirectional"))
    )
    (net (code "112") (name "/~{OE}") (class "Default")
      (node (ref "U1") (pin "114") (pinfunction "IO_L65N_SCP2_0_114") (pintype "bidirectional+no_connect"))
    )
    (net (code "113") (name "/~{RAS}") (class "Default")
      (node (ref "U1") (pin "44") (pinfunction "IO_L62P_D5_2_44") (pintype "bidirectional"))
    )
    (net (code "114") (name "/~{RD}") (class "Default")
      (node (ref "U1") (pin "124") (pinfunction "IO_L37P_GCLK13_0_124") (pintype "bidirectional+no_connect"))
    )
    (net (code "115") (name "/~{RXF}") (class "Default")
      (node (ref "U1") (pin "117") (pinfunction "IO_L64P_SCP5_0_117") (pintype "bidirectional+no_connect"))
    )
    (net (code "116") (name "/~{TXE}") (class "Default")
      (node (ref "U1") (pin "126") (pinfunction "IO_L36N_GCLK14_0_126") (pintype "bidirectional+no_connect"))
    )
    (net (code "117") (name "/~{WE}") (class "Default")
      (node (ref "U1") (pin "46") (pinfunction "IO_L49P_D3_2_46") (pintype "bidirectional"))
    )
    (net (code "118") (name "/~{WR}") (class "Default")
      (node (ref "U1") (pin "121") (pinfunction "IO_L62P_0_121") (pintype "bidirectional+no_connect"))
    )
    (net (code "119") (name "GND") (class "Default")
      (node (ref "C10") (pin "1") (pinfunction "1_1") (pintype "passive"))
      (node (ref "C11") (pin "1") (pinfunction "1_1") (pintype "passive"))
      (node (ref "C12") (pin "1") (pinfunction "1_1") (pintype "passive"))
      (node (ref "C13") (pin "1") (pinfunction "1_1") (pintype "passive"))
      (node (ref "C14") (pin "1") (pinfunction "1_1") (pintype "passive"))
      (node (ref "C15") (pin "1") (pinfunction "1_1") (pintype "passive"))
      (node (ref "C16") (pin "1") (pinfunction "1_1") (pintype "passive"))
      (node (ref "C17") (pin "1") (pinfunction "1_1") (pintype "passive"))
      (node (ref "C18") (pin "1") (pinfunction "1_1") (pintype "passive"))
      (node (ref "C19") (pin "1") (pinfunction "1_1") (pintype "passive"))
      (node (ref "C20") (pin "1") (pinfunction "1_1") (pintype "passive"))
      (node (ref "C21") (pin "1") (pinfunction "1_1") (pintype "passive"))
      (node (ref "C22") (pin "1") (pinfunction "1_1") (pintype "passive"))
      (node (ref "C23") (pin "1") (pinfunction "1_1") (pintype "passive"))
      (node (ref "C24") (pin "1") (pinfunction "1_1") (pintype "passive"))
      (node (ref "C25") (pin "1") (pinfunction "1_1") (pintype "passive"))
      (node (ref "C26") (pin "1") (pinfunction "1_1") (pintype "passive"))
      (node (ref "C27") (pin "1") (pinfunction "1_1") (pintype "passive"))
      (node (ref "C3") (pin "1") (pinfunction "1_1") (pintype "passive"))
      (node (ref "C4") (pin "1") (pinfunction "1_1") (pintype "passive"))
      (node (ref "C5") (pin "1") (pinfunction "1_1") (pintype "passive"))
      (node (ref "C6") (pin "1") (pinfunction "1_1") (pintype "passive"))
      (node (ref "C7") (pin "1") (pinfunction "1_1") (pintype "passive"))
      (node (ref "C74") (pin "1") (pinfunction "1_1") (pintype "passive"))
      (node (ref "C75") (pin "1") (pinfunction "1_1") (pintype "passive"))
      (node (ref "C8") (pin "1") (pinfunction "1_1") (pintype "passive"))
      (node (ref "C9") (pin "1") (pinfunction "1_1") (pintype "passive"))
      (node (ref "J1") (pin "6") (pinfunction "6_6") (pintype "passive"))
      (node (ref "LED3") (pin "2") (pinfunction "2_2") (pintype "passive"))
      (node (ref "S3") (pin "3") (pinfunction "B_3") (pintype "passive"))
      (node (ref "S3") (pin "4") (pinfunction "B'_4") (pintype "passive"))
      (node (ref "S3") (pin "5") (pinfunction "GND_5") (pintype "passive"))
      (node (ref "S3") (pin "6") (pinfunction "GND_6") (pintype "passive"))
      (node (ref "S4") (pin "3") (pinfunction "B_3") (pintype "passive"))
      (node (ref "S4") (pin "4") (pinfunction "B'_4") (pintype "passive"))
      (node (ref "S4") (pin "5") (pinfunction "GND_5") (pintype "passive"))
      (node (ref "S4") (pin "6") (pinfunction "GND_6") (pintype "passive"))
      (node (ref "U1") (pin "108") (pinfunction "GND_108") (pintype "power_in"))
      (node (ref "U1") (pin "113") (pinfunction "GND_113") (pintype "power_in"))
      (node (ref "U1") (pin "13") (pinfunction "GND_13") (pintype "power_in"))
      (node (ref "U1") (pin "130") (pinfunction "GND_130") (pintype "power_in"))
      (node (ref "U1") (pin "136") (pinfunction "GND_136") (pintype "power_in"))
      (node (ref "U1") (pin "144") (pinfunction "IO_L1P_HSWAPEN_0_144") (pintype "bidirectional"))
      (node (ref "U1") (pin "25") (pinfunction "GND_25") (pintype "power_in"))
      (node (ref "U1") (pin "3") (pinfunction "GND_3") (pintype "power_in"))
      (node (ref "U1") (pin "49") (pinfunction "GND_49") (pintype "power_in"))
      (node (ref "U1") (pin "54") (pinfunction "GND_54") (pintype "power_in"))
      (node (ref "U1") (pin "68") (pinfunction "GND_68") (pintype "power_in"))
      (node (ref "U1") (pin "73") (pinfunction "SUSPEND_73") (pintype "input"))
      (node (ref "U1") (pin "77") (pinfunction "GND_77") (pintype "power_in"))
      (node (ref "U1") (pin "91") (pinfunction "GND_91") (pintype "power_in"))
      (node (ref "U1") (pin "96") (pinfunction "GND_96") (pintype "power_in"))
      (node (ref "U2") (pin "2") (pinfunction "GND_2") (pintype "passive"))
    )
    (net (code "120") (name "V1P2") (class "Default")
      (node (ref "C15") (pin "2") (pinfunction "2_2") (pintype "passive"))
      (node (ref "C16") (pin "2") (pinfunction "2_2") (pintype "passive"))
      (node (ref "C17") (pin "2") (pinfunction "2_2") (pintype "passive"))
      (node (ref "C18") (pin "2") (pinfunction "2_2") (pintype "passive"))
      (node (ref "U1") (pin "128") (pinfunction "VCCINT_128") (pintype "power_in"))
      (node (ref "U1") (pin "19") (pinfunction "VCCINT_19") (pintype "power_in"))
      (node (ref "U1") (pin "28") (pinfunction "VCCINT_28") (pintype "power_in"))
      (node (ref "U1") (pin "52") (pinfunction "VCCINT_52") (pintype "power_in"))
      (node (ref "U1") (pin "89") (pinfunction "VCCINT_89") (pintype "power_in"))
    )
    (net (code "121") (name "V3P3") (class "Default")
      (node (ref "C10") (pin "2") (pinfunction "2_2") (pintype "passive"))
      (node (ref "C11") (pin "2") (pinfunction "2_2") (pintype "passive"))
      (node (ref "C12") (pin "2") (pinfunction "2_2") (pintype "passive"))
      (node (ref "C13") (pin "2") (pinfunction "2_2") (pintype "passive"))
      (node (ref "C14") (pin "2") (pinfunction "2_2") (pintype "passive"))
      (node (ref "C19") (pin "2") (pinfunction "2_2") (pintype "passive"))
      (node (ref "C20") (pin "2") (pinfunction "2_2") (pintype "passive"))
      (node (ref "C21") (pin "2") (pinfunction "2_2") (pintype "passive"))
      (node (ref "C22") (pin "2") (pinfunction "2_2") (pintype "passive"))
      (node (ref "C23") (pin "2") (pinfunction "2_2") (pintype "passive"))
      (node (ref "C24") (pin "2") (pinfunction "2_2") (pintype "passive"))
      (node (ref "C25") (pin "2") (pinfunction "2_2") (pintype "passive"))
      (node (ref "C26") (pin "2") (pinfunction "2_2") (pintype "passive"))
      (node (ref "C27") (pin "2") (pinfunction "2_2") (pintype "passive"))
      (node (ref "C3") (pin "2") (pinfunction "2_2") (pintype "passive"))
      (node (ref "C4") (pin "2") (pinfunction "2_2") (pintype "passive"))
      (node (ref "C5") (pin "2") (pinfunction "2_2") (pintype "passive"))
      (node (ref "C6") (pin "2") (pinfunction "2_2") (pintype "passive"))
      (node (ref "C7") (pin "2") (pinfunction "2_2") (pintype "passive"))
      (node (ref "C8") (pin "2") (pinfunction "2_2") (pintype "passive"))
      (node (ref "C9") (pin "2") (pinfunction "2_2") (pintype "passive"))
      (node (ref "J1") (pin "1") (pinfunction "1_1") (pintype "passive"))
      (node (ref "R22") (pin "1") (pinfunction "1_1") (pintype "passive"))
      (node (ref "R23") (pin "1") (pinfunction "1_1") (pintype "passive"))
      (node (ref "R24") (pin "1") (pinfunction "1_1") (pintype "passive"))
      (node (ref "R25") (pin "1") (pinfunction "1_1") (pintype "passive"))
      (node (ref "R26") (pin "1") (pinfunction "1_1") (pintype "passive"))
      (node (ref "R7") (pin "1") (pinfunction "1_1") (pintype "passive"))
      (node (ref "R8") (pin "1") (pinfunction "1_1") (pintype "passive"))
      (node (ref "R8") (pin "2") (pinfunction "2_2") (pintype "passive"))
      (node (ref "R9") (pin "1") (pinfunction "1_1") (pintype "passive"))
      (node (ref "U1") (pin "103") (pinfunction "VCCO_1_103") (pintype "power_in"))
      (node (ref "U1") (pin "122") (pinfunction "VCCO_0_122") (pintype "power_in"))
      (node (ref "U1") (pin "125") (pinfunction "VCCO_0_125") (pintype "power_in"))
      (node (ref "U1") (pin "129") (pinfunction "VCCAUX_129") (pintype "power_in"))
      (node (ref "U1") (pin "135") (pinfunction "VCCO_0_135") (pintype "power_in"))
      (node (ref "U1") (pin "18") (pinfunction "VCCO_3_18") (pintype "power_in"))
      (node (ref "U1") (pin "20") (pinfunction "VCCAUX_20") (pintype "power_in"))
      (node (ref "U1") (pin "31") (pinfunction "VCCO_3_31") (pintype "power_in"))
      (node (ref "U1") (pin "36") (pinfunction "VCCAUX_36") (pintype "power_in"))
      (node (ref "U1") (pin "39") (pinfunction "IO_L65P_INIT_B_2_39") (pintype "bidirectional"))
      (node (ref "U1") (pin "4") (pinfunction "VCCO_3_4") (pintype "power_in"))
      (node (ref "U1") (pin "42") (pinfunction "VCCO_2_42") (pintype "power_in"))
      (node (ref "U1") (pin "53") (pinfunction "VCCAUX_53") (pintype "power_in"))
      (node (ref "U1") (pin "63") (pinfunction "VCCO_2_63") (pintype "power_in"))
      (node (ref "U1") (pin "69") (pinfunction "IO_L1N_M0_CMPMISO_2_69") (pintype "bidirectional"))
      (node (ref "U1") (pin "76") (pinfunction "VCCO_1_76") (pintype "power_in"))
      (node (ref "U1") (pin "86") (pinfunction "VCCO_1_86") (pintype "power_in"))
      (node (ref "U1") (pin "90") (pinfunction "VCCAUX_90") (pintype "power_in"))
      (node (ref "U2") (pin "1") (pinfunction "EOH_1") (pintype "passive"))
      (node (ref "U2") (pin "4") (pinfunction "VCC_4") (pintype "passive"))
    )
    (net (code "122") (name "unconnected-(S3-A'-Pad2)") (class "Default")
      (node (ref "S3") (pin "2") (pinfunction "A'_2") (pintype "passive+no_connect"))
    )
    (net (code "123") (name "unconnected-(S4-A'-Pad2)") (class "Default")
      (node (ref "S4") (pin "2") (pinfunction "A'_2") (pintype "passive+no_connect"))
    )
    (net (code "124") (name "unconnected-(U1A-IO_L66P_SCP1_0-Pad112)") (class "Default")
      (node (ref "U1") (pin "112") (pinfunction "IO_L66P_SCP1_0_112") (pintype "bidirectional+no_connect"))
    )
    (net (code "125") (name "unconnected-(U1E-CMPCS_B_2-Pad72)") (class "Default")
      (node (ref "U1") (pin "72") (pinfunction "CMPCS_B_2_72") (pintype "input+no_connect"))
    )
  )
)
